# Over_current_Over_voltage_Decoupling.net
KiCad netlist of a schematic drawn in EAGLE
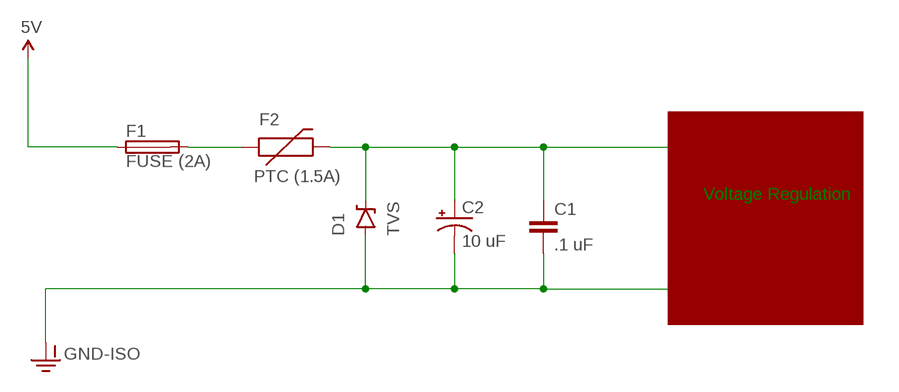
[diagram p0: schematic, sheet 1]

(export (version "E")
  (design (tool "Eeschema 10.0.6"))
  (components
    (comp (ref "C1")
      (value ".1 uF")
      (footprint "eagle-import:1206")
      (libsource (lib "eagle-import") (part "CAP1206"))
    )
    (comp (ref "C2")
      (value "10 uF")
      (footprint "eagle-import:CPOL-RADIAL-10UF-25V")
      (libsource (lib "eagle-import") (part "CAP_POLPTH2"))
    )
    (comp (ref "D1")
      (value "TVS")
      (footprint "eagle-import:DIODE-ZENER")
      (libsource (lib "eagle-import") (part "DIODE-ZENERPTH"))
    )
    (comp (ref "F1")
      (value "FUSE (2A)")
      (footprint "eagle-import:FUSE_HOLDER_MENTOR-1821")
      (libsource (lib "eagle-import") (part "FUSE1821"))
    )
    (comp (ref "F2")
      (value "PTC (1.5A)")
      (footprint "eagle-import:PTC")
      (libsource (lib "eagle-import") (part "PTCPTH"))
    )
  )
  (nets
    (net (code "1") (name "5V") (class "Default")
      (node (ref "F1") (pin "A") (pinfunction "1_A") (pintype "passive"))
    )
    (net (code "2") (name "GND-ISO") (class "Default")
      (node (ref "C1") (pin "2") (pinfunction "2_2") (pintype "passive"))
      (node (ref "C2") (pin "2") (pinfunction "-_2") (pintype "passive"))
      (node (ref "D1") (pin "P$2") (pinfunction "A_P$2") (pintype "passive"))
    )
    (net (code "3") (name "Net-(C2-+)") (class "Default")
      (node (ref "C1") (pin "1") (pinfunction "1_1") (pintype "passive"))
      (node (ref "C2") (pin "1") (pinfunction "+_1") (pintype "passive"))
      (node (ref "D1") (pin "P$1") (pinfunction "C_P$1") (pintype "passive"))
      (node (ref "F2") (pin "P$2") (pinfunction "2_P$2") (pintype "bidirectional"))
    )
    (net (code "4") (name "Net-(F1-2)") (class "Default")
      (node (ref "F1") (pin "B") (pinfunction "2_B") (pintype "passive"))
      (node (ref "F2") (pin "P$1") (pinfunction "1_P$1") (pintype "bidirectional"))
    )
  )
)
